# kgopalak_TH.net
KiCad netlist of a schematic drawn in EAGLE
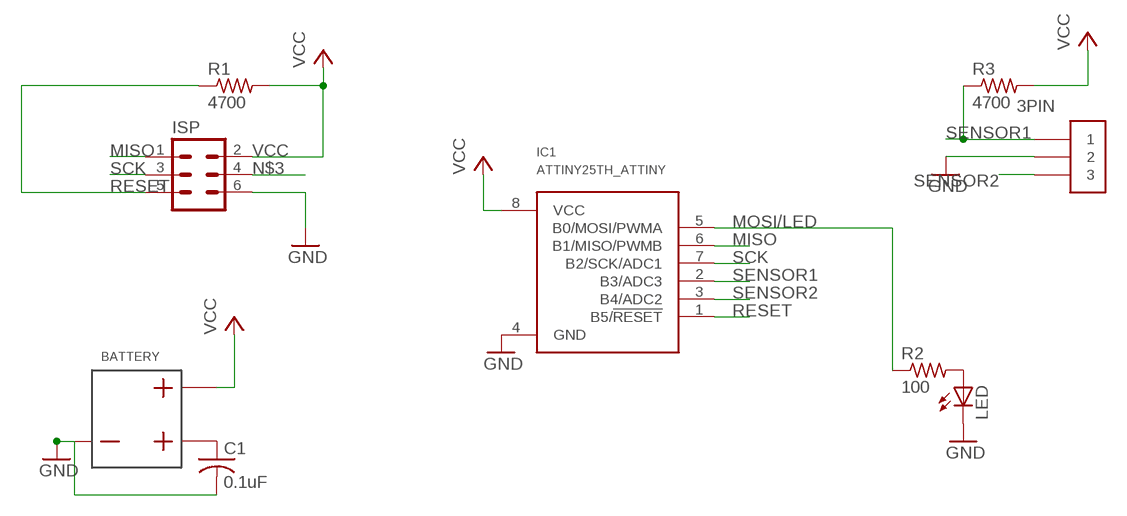
[diagram p0: schematic, sheet 1]

(export (version "E")
  (design (tool "Eeschema 10.0.6"))
  (components
    (comp (ref "3PIN")
      (value "3PINCONTH_3PIN")
      (footprint "eagle-import:PUSHCON3")
      (libsource (lib "eagle-import") (part "3PINCONTH_3PIN"))
    )
    (comp (ref "BATTERY")
      (value "BATTERYTH_BA2032")
      (footprint "eagle-import:BA2032")
      (libsource (lib "eagle-import") (part "BATTERYTH_BA2032"))
    )
    (comp (ref "C1")
      (value "0.1uF")
      (footprint "eagle-import:C025-025X050")
      (libsource (lib "eagle-import") (part "CAPACITORTH_CAP"))
    )
    (comp (ref "IC1")
      (value "ATTINY25TH_ATTINY")
      (footprint "eagle-import:DIL08")
      (libsource (lib "eagle-import") (part "ATTINY25TH_ATTINY"))
    )
    (comp (ref "ISP")
      (value "6PINCON_ISPTH_6PIN")
      (footprint "eagle-import:6P2R0.1IN")
      (libsource (lib "eagle-import") (part "6PINCON_ISPTH_6PIN"))
    )
    (comp (ref "LED")
      (value "LEDTH_LED")
      (footprint "eagle-import:LED5MM")
      (libsource (lib "eagle-import") (part "LEDTH_LED"))
    )
    (comp (ref "R1")
      (value "4700")
      (footprint "eagle-import:0204_7")
      (libsource (lib "eagle-import") (part "RESISTORTH_RESISTOR"))
    )
    (comp (ref "R2")
      (value "100")
      (footprint "eagle-import:0204_7")
      (libsource (lib "eagle-import") (part "RESISTORTH_RESISTOR"))
    )
    (comp (ref "R3")
      (value "4700")
      (footprint "eagle-import:0204_7")
      (libsource (lib "eagle-import") (part "RESISTORTH_RESISTOR"))
    )
  )
  (nets
    (net (code "1") (name "/MISO") (class "Default")
      (node (ref "IC1") (pin "6") (pinfunction "B1/MISO/PWMB_6") (pintype "bidirectional"))
      (node (ref "ISP") (pin "1") (pinfunction "1_1") (pintype "bidirectional"))
    )
    (net (code "2") (name "/MOSI{slash}LED") (class "Default")
      (node (ref "IC1") (pin "5") (pinfunction "B0/MOSI/PWMA_5") (pintype "bidirectional"))
      (node (ref "R2") (pin "1") (pinfunction "1_1") (pintype "bidirectional"))
    )
    (net (code "3") (name "/N$3") (class "Default")
      (node (ref "ISP") (pin "4") (pinfunction "4_4") (pintype "bidirectional"))
    )
    (net (code "4") (name "/RESET") (class "Default")
      (node (ref "IC1") (pin "1") (pinfunction "B5/~{RESET}_1") (pintype "bidirectional"))
      (node (ref "ISP") (pin "5") (pinfunction "5_5") (pintype "bidirectional"))
      (node (ref "R1") (pin "1") (pinfunction "1_1") (pintype "bidirectional"))
    )
    (net (code "5") (name "/SCK") (class "Default")
      (node (ref "IC1") (pin "7") (pinfunction "B2/SCK/ADC1_7") (pintype "bidirectional"))
      (node (ref "ISP") (pin "3") (pinfunction "3_3") (pintype "bidirectional"))
    )
    (net (code "6") (name "/SENSOR1") (class "Default")
      (node (ref "3PIN") (pin "1") (pinfunction "1_1") (pintype "bidirectional"))
      (node (ref "IC1") (pin "2") (pinfunction "B3/ADC3_2") (pintype "bidirectional"))
      (node (ref "R3") (pin "1") (pinfunction "1_1") (pintype "bidirectional"))
    )
    (net (code "7") (name "/SENSOR2") (class "Default")
      (node (ref "3PIN") (pin "3") (pinfunction "3_3") (pintype "bidirectional"))
      (node (ref "IC1") (pin "3") (pinfunction "B4/ADC2_3") (pintype "bidirectional"))
    )
    (net (code "8") (name "GND") (class "Default")
      (node (ref "3PIN") (pin "2") (pinfunction "2_2") (pintype "bidirectional"))
      (node (ref "BATTERY") (pin "P$1") (pinfunction "P$1_P$1") (pintype "bidirectional"))
      (node (ref "C1") (pin "2") (pinfunction "2_2") (pintype "bidirectional"))
      (node (ref "IC1") (pin "4") (pinfunction "GND_4") (pintype "bidirectional"))
      (node (ref "ISP") (pin "6") (pinfunction "6_6") (pintype "bidirectional"))
      (node (ref "LED") (pin "K") (pinfunction "C_K") (pintype "bidirectional"))
    )
    (net (code "9") (name "Net-(BATTERY-PadP$3)") (class "Default")
      (node (ref "BATTERY") (pin "P$3") (pinfunction "P$3_P$3") (pintype "bidirectional"))
      (node (ref "C1") (pin "1") (pinfunction "1_1") (pintype "bidirectional"))
    )
    (net (code "10") (name "Net-(LED-PadA)") (class "Default")
      (node (ref "LED") (pin "A") (pinfunction "A_A") (pintype "bidirectional"))
      (node (ref "R2") (pin "2") (pinfunction "2_2") (pintype "bidirectional"))
    )
    (net (code "11") (name "VCC") (class "Default")
      (node (ref "BATTERY") (pin "P$2") (pinfunction "P$2_P$2") (pintype "bidirectional"))
      (node (ref "IC1") (pin "8") (pinfunction "VCC_8") (pintype "bidirectional"))
      (node (ref "ISP") (pin "2") (pinfunction "2_2") (pintype "bidirectional"))
      (node (ref "R1") (pin "2") (pinfunction "2_2") (pintype "bidirectional"))
      (node (ref "R3") (pin "2") (pinfunction "2_2") (pintype "bidirectional"))
    )
  )
)
